# SW1106_100W_C_SH2.net
KiCad netlist of a schematic drawn in Altium Designer
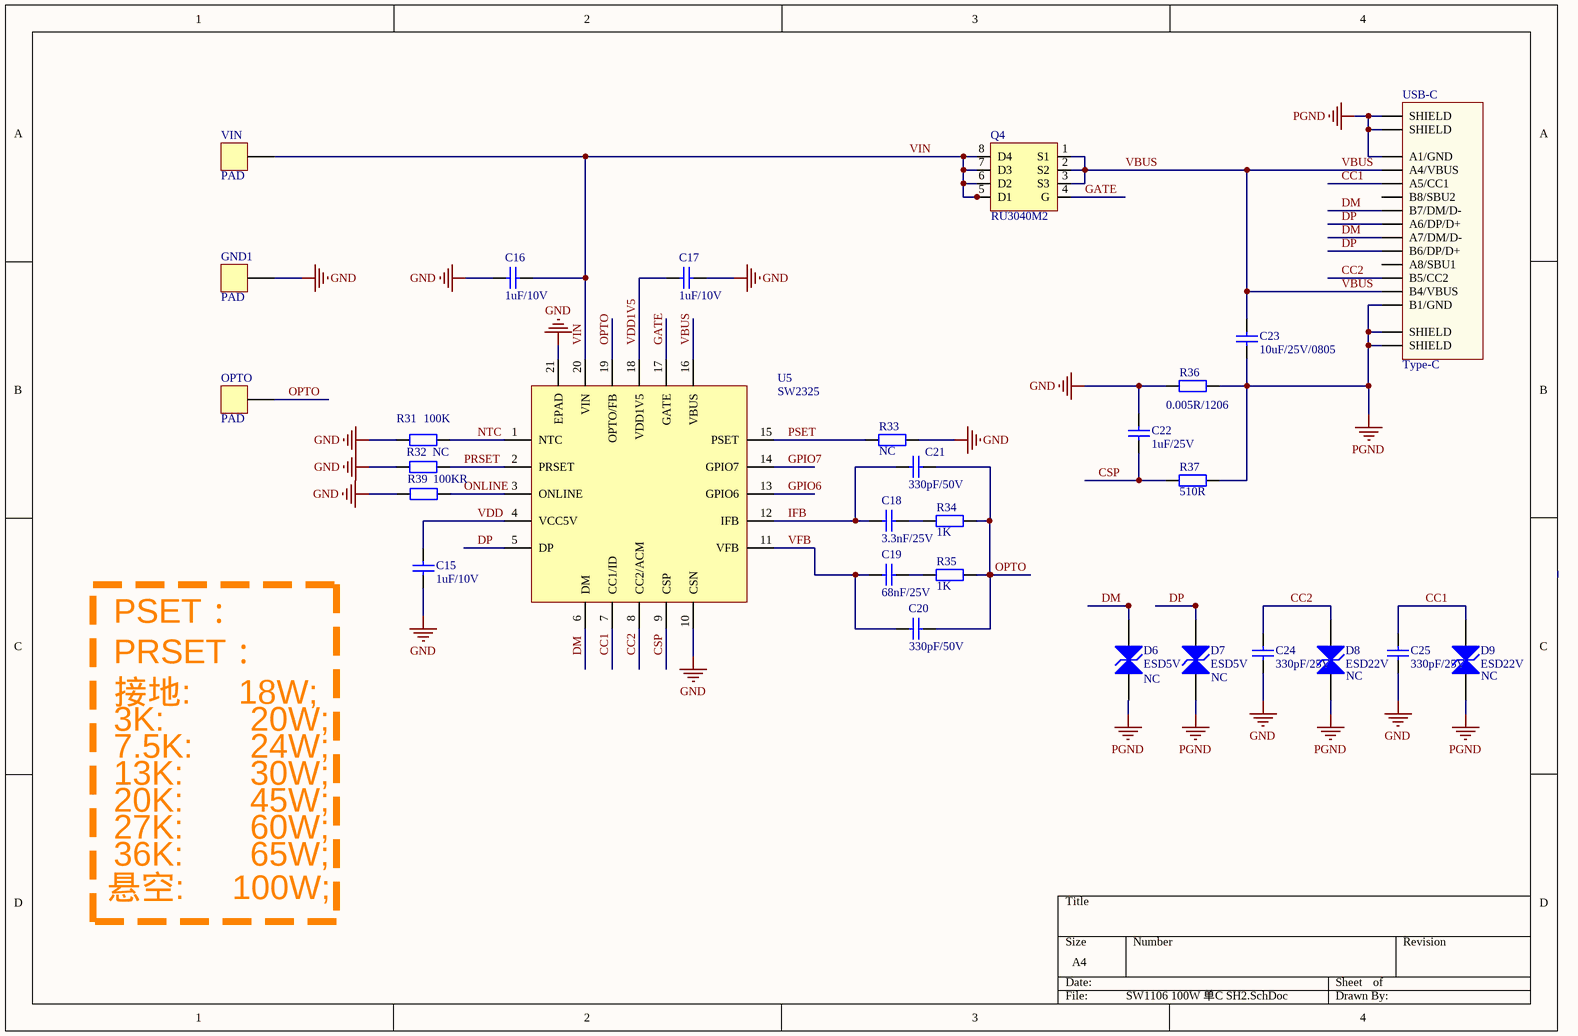
[diagram p0: SW1106 100W 单C SH2.SchDoc]

(export (version "E")
  (design (tool "Eeschema 10.0.6"))
  (components
    (comp (ref "C15")
      (value "1uF/10V")
      (footprint "C 0603")
      (description "电容-无极性")
      (libsource (lib "LwpBaseSchlib") (part "Capacitor"))
    )
    (comp (ref "C16")
      (value "1uF/10V")
      (footprint "C 0603")
      (description "电容-无极性")
      (libsource (lib "LwpBaseSchlib") (part "Capacitor"))
    )
    (comp (ref "C17")
      (value "1uF/10V")
      (footprint "C 0603")
      (description "电容-无极性")
      (libsource (lib "LwpBaseSchlib") (part "Capacitor"))
    )
    (comp (ref "C18")
      (value "3.3nF/25V")
      (footprint "C 0603")
      (description "电容-无极性")
      (libsource (lib "LwpBaseSchlib") (part "Capacitor"))
    )
    (comp (ref "C19")
      (value "68nF/25V")
      (footprint "C 0603")
      (description "电容-无极性")
      (libsource (lib "LwpBaseSchlib") (part "Capacitor"))
    )
    (comp (ref "C20")
      (value "330pF/50V")
      (footprint "C 0603")
      (description "电容-无极性")
      (libsource (lib "LwpBaseSchlib") (part "Capacitor"))
    )
    (comp (ref "C21")
      (value "330pF/50V")
      (footprint "C 0603")
      (description "电容-无极性")
      (libsource (lib "LwpBaseSchlib") (part "Capacitor"))
    )
    (comp (ref "C22")
      (value "1uF/25V")
      (footprint "C 0603")
      (description "电容-无极性")
      (libsource (lib "LwpBaseSchlib") (part "Capacitor"))
    )
    (comp (ref "C23")
      (value "10uF/25V/0805")
      (footprint "C 0805")
      (description "电容-无极性")
      (libsource (lib "LwpBaseSchlib") (part "Capacitor"))
    )
    (comp (ref "C24")
      (value "330pF/25V")
      (footprint "C 0603")
      (description "电容-无极性")
      (libsource (lib "LwpBaseSchlib") (part "Capacitor"))
    )
    (comp (ref "C25")
      (value "330pF/25V")
      (footprint "C 0603")
      (description "电容-无极性")
      (libsource (lib "LwpBaseSchlib") (part "Capacitor"))
    )
    (comp (ref "D6")
      (value "ESD5V")
      (footprint "SOD-523")
      (description "防静电二极管")
      (libsource (lib "LwpBaseSchlib") (part "Diode_ESD"))
    )
    (comp (ref "D7")
      (value "ESD5V")
      (footprint "SOD-523")
      (description "防静电二极管")
      (libsource (lib "LwpBaseSchlib") (part "Diode_ESD"))
    )
    (comp (ref "D8")
      (value "ESD22V")
      (footprint "SOD-523")
      (description "防静电二极管")
      (libsource (lib "LwpBaseSchlib") (part "Diode_ESD"))
    )
    (comp (ref "D9")
      (value "ESD22V")
      (footprint "SOD-523")
      (description "防静电二极管")
      (libsource (lib "LwpBaseSchlib") (part "Diode_ESD"))
    )
    (comp (ref "GND1") (value "PAD") (footprint "PAD") (libsource (lib "LwpBaseSchlib") (part "PAD")))
    (comp (ref "OPTO") (value "PAD") (footprint "PAD") (libsource (lib "LwpBaseSchlib") (part "PAD")))
    (comp (ref "Q4")
      (value "RU3040M2")
      (footprint "PDFN-3*3")
      (description "PDFN封装N-MOS")
      (libsource (lib "LwpBaseSchlib") (part "MOSFET-PDFN"))
    )
    (comp (ref "R31")
      (value "100K")
      (footprint "R 0603")
      (description "电阻")
      (libsource (lib "LwpBaseSchlib") (part "Resistance"))
    )
    (comp (ref "R32")
      (value "NC")
      (footprint "R 0603")
      (description "电阻")
      (libsource (lib "LwpBaseSchlib") (part "Resistance"))
    )
    (comp (ref "R33")
      (value "NC")
      (footprint "R 0603")
      (description "电阻")
      (libsource (lib "LwpBaseSchlib") (part "Resistance"))
    )
    (comp (ref "R34")
      (value "1K")
      (footprint "R 0603")
      (description "电阻")
      (libsource (lib "LwpBaseSchlib") (part "Resistance"))
    )
    (comp (ref "R35")
      (value "1K")
      (footprint "R 0603")
      (description "电阻")
      (libsource (lib "LwpBaseSchlib") (part "Resistance"))
    )
    (comp (ref "R36")
      (value "0.005R/1206")
      (footprint "R 1206")
      (description "电阻")
      (libsource (lib "LwpBaseSchlib") (part "Resistance"))
    )
    (comp (ref "R37")
      (value "510R")
      (footprint "R 0603")
      (description "电阻")
      (libsource (lib "LwpBaseSchlib") (part "Resistance"))
    )
    (comp (ref "R39")
      (value "100KR")
      (footprint "R 0603")
      (description "电阻")
      (libsource (lib "LwpBaseSchlib") (part "Resistance"))
    )
    (comp (ref "U5")
      (value "SW2325")
      (footprint "SW232X_QFN20-4X4")
      (description "智融科技SW2325")
      (libsource (lib "智融IC") (part "SW2325"))
    )
    (comp (ref "USB-C")
      (value "Type-C")
      (footprint "USB_C_16PIN")
      (description "USB-C")
      (libsource (lib "LwpSchlib") (part "Type-C_16Pin"))
    )
    (comp (ref "VIN") (value "PAD") (footprint "PAD") (libsource (lib "LwpBaseSchlib") (part "PAD")))
  )
  (nets
    (net (code "1") (name "/CC1") (class "Default")
      (node (ref "C25") (pin "2") (pinfunction "2_2") (pintype "passive"))
      (node (ref "D9") (pin "2") (pinfunction "K_2") (pintype "passive"))
      (node (ref "U5") (pin "7") (pinfunction "CC1/ID_7") (pintype "passive"))
      (node (ref "USB-C") (pin "A5") (pinfunction "A5/CC1_A5") (pintype "passive"))
    )
    (net (code "2") (name "/CC2") (class "Default")
      (node (ref "C24") (pin "2") (pinfunction "2_2") (pintype "passive"))
      (node (ref "D8") (pin "2") (pinfunction "K_2") (pintype "passive"))
      (node (ref "U5") (pin "8") (pinfunction "CC2/ACM_8") (pintype "passive"))
      (node (ref "USB-C") (pin "B5") (pinfunction "B5/CC2_B5") (pintype "passive"))
    )
    (net (code "3") (name "/CSP") (class "Default")
      (node (ref "C22") (pin "1") (pinfunction "1_1") (pintype "passive"))
      (node (ref "R37") (pin "1") (pinfunction "1_1") (pintype "passive"))
      (node (ref "U5") (pin "9") (pinfunction "CSP_9") (pintype "passive"))
    )
    (net (code "4") (name "/DM") (class "Default")
      (node (ref "D6") (pin "2") (pinfunction "K_2") (pintype "passive"))
      (node (ref "U5") (pin "6") (pinfunction "DM_6") (pintype "passive"))
      (node (ref "USB-C") (pin "A7") (pinfunction "A7/DM/D-_A7") (pintype "passive"))
      (node (ref "USB-C") (pin "B7") (pinfunction "B7/DM/D-_B7") (pintype "passive"))
    )
    (net (code "5") (name "/DP") (class "Default")
      (node (ref "D7") (pin "2") (pinfunction "K_2") (pintype "passive"))
      (node (ref "U5") (pin "5") (pinfunction "DP_5") (pintype "passive"))
      (node (ref "USB-C") (pin "A6") (pinfunction "A6/DP/D+_A6") (pintype "passive"))
      (node (ref "USB-C") (pin "B6") (pinfunction "B6/DP/D+_B6") (pintype "passive"))
    )
    (net (code "6") (name "/GATE") (class "Default")
      (node (ref "Q4") (pin "4") (pinfunction "G_4") (pintype "passive"))
      (node (ref "U5") (pin "17") (pinfunction "GATE_17") (pintype "passive"))
    )
    (net (code "7") (name "/GPIO6") (class "Default")
      (node (ref "U5") (pin "13") (pinfunction "GPIO6_13") (pintype "passive"))
    )
    (net (code "8") (name "/GPIO7") (class "Default")
      (node (ref "U5") (pin "14") (pinfunction "GPIO7_14") (pintype "passive"))
    )
    (net (code "9") (name "/IFB") (class "Default")
      (node (ref "C18") (pin "1") (pinfunction "1_1") (pintype "passive"))
      (node (ref "C21") (pin "1") (pinfunction "1_1") (pintype "passive"))
      (node (ref "U5") (pin "12") (pinfunction "IFB_12") (pintype "passive"))
    )
    (net (code "10") (name "/NTC") (class "Default")
      (node (ref "R31") (pin "2") (pinfunction "2_2") (pintype "passive"))
      (node (ref "U5") (pin "1") (pinfunction "NTC_1") (pintype "passive"))
    )
    (net (code "11") (name "/ONLINE") (class "Default")
      (node (ref "R39") (pin "2") (pinfunction "2_2") (pintype "passive"))
      (node (ref "U5") (pin "3") (pinfunction "ONLINE_3") (pintype "passive"))
    )
    (net (code "12") (name "/OPTO") (class "Default")
      (node (ref "C20") (pin "2") (pinfunction "2_2") (pintype "passive"))
      (node (ref "C21") (pin "2") (pinfunction "2_2") (pintype "passive"))
      (node (ref "OPTO") (pin "1") (pinfunction "PAD_1") (pintype "passive"))
      (node (ref "R34") (pin "2") (pinfunction "2_2") (pintype "passive"))
      (node (ref "R35") (pin "2") (pinfunction "2_2") (pintype "passive"))
      (node (ref "U5") (pin "19") (pinfunction "OPTO/FB_19") (pintype "passive"))
    )
    (net (code "13") (name "/PRSET") (class "Default")
      (node (ref "R32") (pin "2") (pinfunction "2_2") (pintype "passive"))
      (node (ref "U5") (pin "2") (pinfunction "PRSET_2") (pintype "passive"))
    )
    (net (code "14") (name "/PSET") (class "Default")
      (node (ref "R33") (pin "1") (pinfunction "1_1") (pintype "passive"))
      (node (ref "U5") (pin "15") (pinfunction "PSET_15") (pintype "passive"))
    )
    (net (code "15") (name "/VBUS") (class "Default")
      (node (ref "C23") (pin "2") (pinfunction "2_2") (pintype "passive"))
      (node (ref "Q4") (pin "1") (pinfunction "S1_1") (pintype "passive"))
      (node (ref "Q4") (pin "2") (pinfunction "S2_2") (pintype "passive"))
      (node (ref "Q4") (pin "3") (pinfunction "S3_3") (pintype "passive"))
      (node (ref "U5") (pin "16") (pinfunction "VBUS_16") (pintype "passive"))
      (node (ref "USB-C") (pin "A4") (pinfunction "A4/VBUS_A4") (pintype "passive"))
      (node (ref "USB-C") (pin "B4") (pinfunction "B4/VBUS_B4") (pintype "passive"))
    )
    (net (code "16") (name "/VDD") (class "Default")
      (node (ref "C15") (pin "2") (pinfunction "2_2") (pintype "passive"))
      (node (ref "U5") (pin "4") (pinfunction "VCC5V_4") (pintype "passive"))
    )
    (net (code "17") (name "/VDD1V5") (class "Default")
      (node (ref "C17") (pin "2") (pinfunction "2_2") (pintype "passive"))
      (node (ref "U5") (pin "18") (pinfunction "VDD1V5_18") (pintype "passive"))
    )
    (net (code "18") (name "/VFB") (class "Default")
      (node (ref "C19") (pin "1") (pinfunction "1_1") (pintype "passive"))
      (node (ref "C20") (pin "1") (pinfunction "1_1") (pintype "passive"))
      (node (ref "U5") (pin "11") (pinfunction "VFB_11") (pintype "passive"))
    )
    (net (code "19") (name "/VIN") (class "Default")
      (node (ref "C16") (pin "2") (pinfunction "2_2") (pintype "passive"))
      (node (ref "Q4") (pin "5") (pinfunction "D1_5") (pintype "passive"))
      (node (ref "Q4") (pin "6") (pinfunction "D2_6") (pintype "passive"))
      (node (ref "Q4") (pin "7") (pinfunction "D3_7") (pintype "passive"))
      (node (ref "Q4") (pin "8") (pinfunction "D4_8") (pintype "passive"))
      (node (ref "Q4") (pin "9") (pinfunction "EPAD_9") (pintype "passive"))
      (node (ref "U5") (pin "20") (pinfunction "VIN_20") (pintype "passive"))
      (node (ref "VIN") (pin "1") (pinfunction "PAD_1") (pintype "passive"))
    )
    (net (code "20") (name "GND") (class "Default")
      (node (ref "C15") (pin "1") (pinfunction "1_1") (pintype "passive"))
      (node (ref "C16") (pin "1") (pinfunction "1_1") (pintype "passive"))
      (node (ref "C17") (pin "1") (pinfunction "1_1") (pintype "passive"))
      (node (ref "C22") (pin "2") (pinfunction "2_2") (pintype "passive"))
      (node (ref "C24") (pin "1") (pinfunction "1_1") (pintype "passive"))
      (node (ref "C25") (pin "1") (pinfunction "1_1") (pintype "passive"))
      (node (ref "GND1") (pin "1") (pinfunction "PAD_1") (pintype "passive"))
      (node (ref "R31") (pin "1") (pinfunction "1_1") (pintype "passive"))
      (node (ref "R32") (pin "1") (pinfunction "1_1") (pintype "passive"))
      (node (ref "R33") (pin "2") (pinfunction "2_2") (pintype "passive"))
      (node (ref "R36") (pin "1") (pinfunction "1_1") (pintype "passive"))
      (node (ref "R39") (pin "1") (pinfunction "1_1") (pintype "passive"))
      (node (ref "U5") (pin "10") (pinfunction "CSN_10") (pintype "passive"))
      (node (ref "U5") (pin "21") (pinfunction "EPAD_21") (pintype "passive"))
    )
    (net (code "21") (name "Net-(C18-Pad2)") (class "Default")
      (node (ref "C18") (pin "2") (pinfunction "2_2") (pintype "passive"))
      (node (ref "R34") (pin "1") (pinfunction "1_1") (pintype "passive"))
    )
    (net (code "22") (name "Net-(C19-Pad2)") (class "Default")
      (node (ref "C19") (pin "2") (pinfunction "2_2") (pintype "passive"))
      (node (ref "R35") (pin "1") (pinfunction "1_1") (pintype "passive"))
    )
    (net (code "23") (name "PGND") (class "Default")
      (node (ref "C23") (pin "1") (pinfunction "1_1") (pintype "passive"))
      (node (ref "D6") (pin "1") (pinfunction "A_1") (pintype "passive"))
      (node (ref "D7") (pin "1") (pinfunction "A_1") (pintype "passive"))
      (node (ref "D8") (pin "1") (pinfunction "A_1") (pintype "passive"))
      (node (ref "D9") (pin "1") (pinfunction "A_1") (pintype "passive"))
      (node (ref "R36") (pin "2") (pinfunction "2_2") (pintype "passive"))
      (node (ref "R37") (pin "2") (pinfunction "2_2") (pintype "passive"))
      (node (ref "USB-C") (pin "1") (pinfunction "SHIELD_1") (pintype "passive"))
      (node (ref "USB-C") (pin "2") (pinfunction "SHIELD_2") (pintype "passive"))
      (node (ref "USB-C") (pin "3") (pinfunction "SHIELD_3") (pintype "passive"))
      (node (ref "USB-C") (pin "4") (pinfunction "SHIELD_4") (pintype "passive"))
      (node (ref "USB-C") (pin "A1") (pinfunction "A1/GND_A1") (pintype "passive"))
      (node (ref "USB-C") (pin "B1") (pinfunction "B1/GND_B1") (pintype "passive"))
    )
    (net (code "24") (name "unconnected-(USB-C-A8{slash}SBU1-PadA8)") (class "Default")
      (node (ref "USB-C") (pin "A8") (pinfunction "A8/SBU1_A8") (pintype "passive"))
    )
    (net (code "25") (name "unconnected-(USB-C-B8{slash}SBU2-PadB8)") (class "Default")
      (node (ref "USB-C") (pin "B8") (pinfunction "B8/SBU2_B8") (pintype "passive"))
    )
  )
)
